# OrientationBoard_LIS303_LIS2DM_L3GD20.net
KiCad netlist of a schematic drawn in Altium Designer
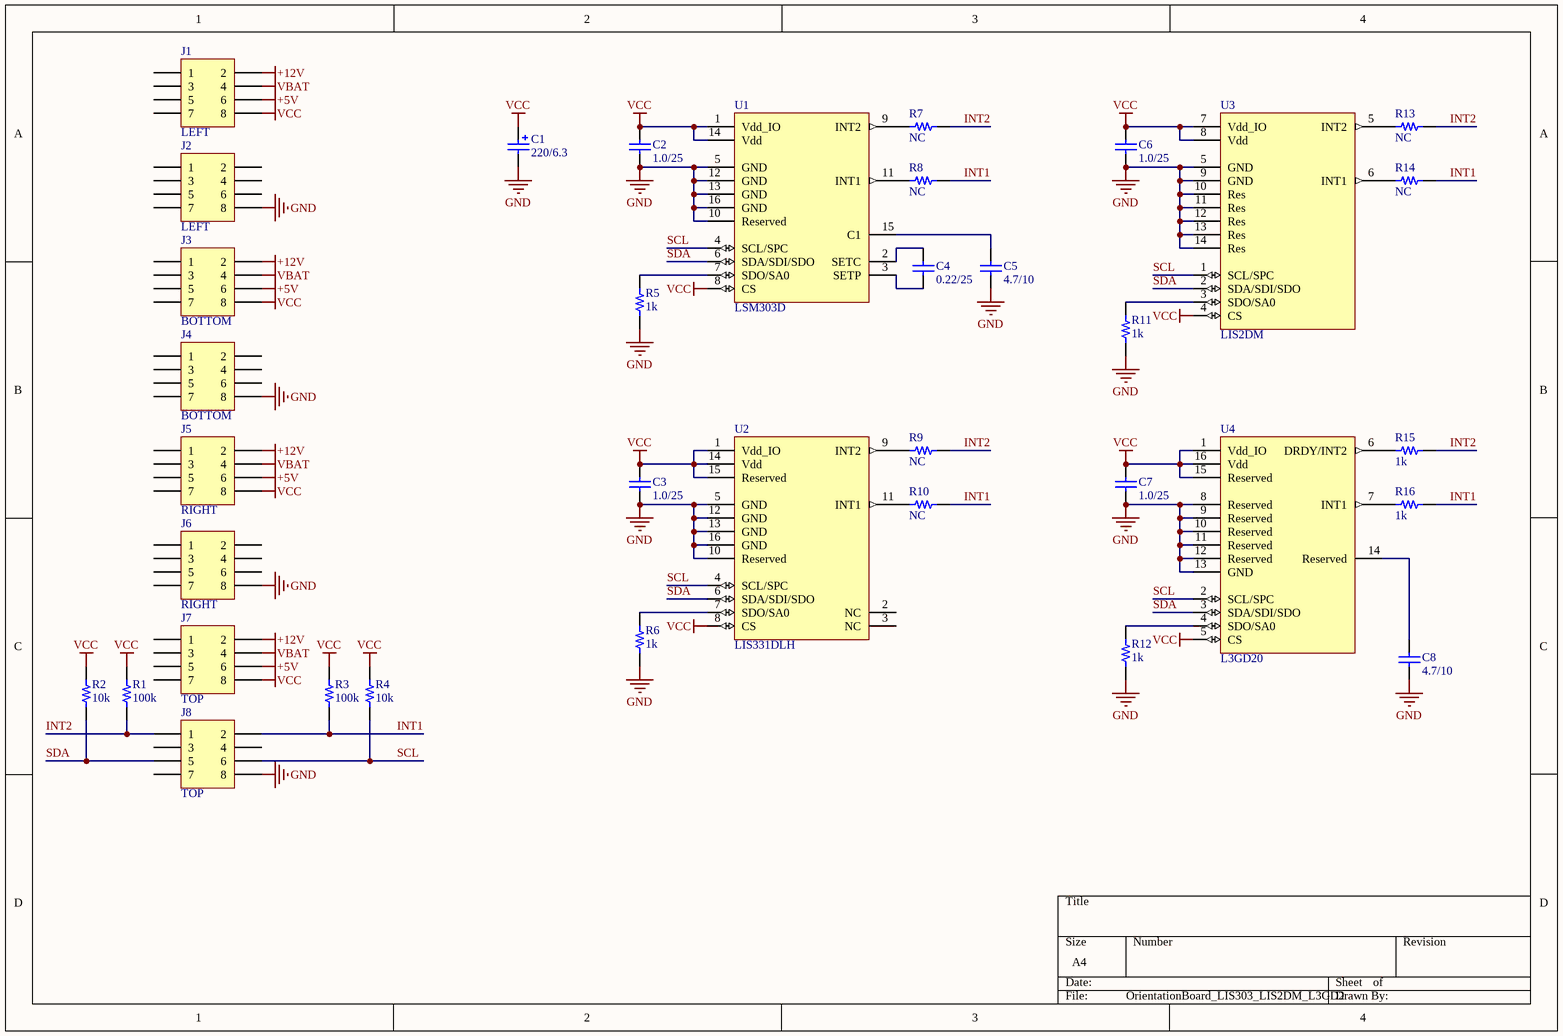
[diagram p0: OrientationBoard_LIS303_LIS2DM_L3GD20.SchDoc]

(export (version "E")
  (design (tool "Eeschema 10.0.6"))
  (components
    (comp (ref "C1")
      (value "220/6.3")
      (footprint "SMC")
      (description "Standard tantalum SMT capacitor, size C")
      (fields
        (field (name "PARTNUMBER") "TAJC")
        (field (name "VOLTAGE") "6.3")
        (field (name "AUTHOR") "oiezhov")
      )
      (libsource (lib "Library") (part "Polar capacitor"))
    )
    (comp (ref "C2")
      (value "1.0/25")
      (footprint "CAP0402")
      (description "Ceramic chip capacitor 0402")
      (fields
        (field (name "PARTNUMBER") "CAP0402")
        (field (name "VOLTAGE") "25")
        (field (name "AUTHOR") "oiezhov")
      )
      (libsource (lib "Library") (part "Capacitor"))
    )
    (comp (ref "C3")
      (value "1.0/25")
      (footprint "CAP0402")
      (description "Ceramic chip capacitor 0402")
      (fields
        (field (name "PARTNUMBER") "CAP0402")
        (field (name "VOLTAGE") "25")
        (field (name "AUTHOR") "oiezhov")
      )
      (libsource (lib "Library") (part "Capacitor"))
    )
    (comp (ref "C4")
      (value "0.22/25")
      (footprint "CAP0402")
      (description "Ceramic chip capacitor 0402")
      (fields
        (field (name "PARTNUMBER") "CAP0402")
        (field (name "VOLTAGE") "25")
        (field (name "AUTHOR") "oiezhov")
      )
      (libsource (lib "Library") (part "Capacitor"))
    )
    (comp (ref "C5")
      (value "4.7/10")
      (footprint "CAP0603")
      (description "Ceramic chip capacitor 0603")
      (fields
        (field (name "PARTNUMBER") "CAP0603")
        (field (name "VOLTAGE") "10")
        (field (name "AUTHOR") "oiezhov")
      )
      (libsource (lib "Library") (part "Capacitor"))
    )
    (comp (ref "C6")
      (value "1.0/25")
      (footprint "CAP0402")
      (description "Ceramic chip capacitor 0402")
      (fields
        (field (name "PARTNUMBER") "CAP0402")
        (field (name "VOLTAGE") "25")
        (field (name "AUTHOR") "oiezhov")
      )
      (libsource (lib "Library") (part "Capacitor"))
    )
    (comp (ref "C7")
      (value "1.0/25")
      (footprint "CAP0402")
      (description "Ceramic chip capacitor 0402")
      (fields
        (field (name "PARTNUMBER") "CAP0402")
        (field (name "VOLTAGE") "25")
        (field (name "AUTHOR") "oiezhov")
      )
      (libsource (lib "Library") (part "Capacitor"))
    )
    (comp (ref "C8")
      (value "4.7/10")
      (footprint "CAP0603")
      (description "Ceramic chip capacitor 0603")
      (fields
        (field (name "PARTNUMBER") "CAP0603")
        (field (name "VOLTAGE") "10")
        (field (name "AUTHOR") "oiezhov")
      )
      (libsource (lib "Library") (part "Capacitor"))
    )
    (comp (ref "J1")
      (value "LEFT")
      (footprint "PBDM-8")
      (description "2x4-pin header, pitch 2.54 mm")
      (fields (field (name "PARTNUMBER") "PBDM-8") (field (name "AUTHOR") "oiezhov"))
      (libsource (lib "Library") (part "8-pin dual row connector"))
    )
    (comp (ref "J2")
      (value "LEFT")
      (footprint "PBDM-8")
      (description "2x4-pin header, pitch 2.54 mm")
      (fields (field (name "PARTNUMBER") "PBDM-8") (field (name "AUTHOR") "oiezhov"))
      (libsource (lib "Library") (part "8-pin dual row connector"))
    )
    (comp (ref "J3")
      (value "BOTTOM")
      (footprint "PBDM-8")
      (description "2x4-pin header, pitch 2.54 mm")
      (fields (field (name "PARTNUMBER") "PBDM-8") (field (name "AUTHOR") "oiezhov"))
      (libsource (lib "Library") (part "8-pin dual row connector"))
    )
    (comp (ref "J4")
      (value "BOTTOM")
      (footprint "PBDM-8")
      (description "2x4-pin header, pitch 2.54 mm")
      (fields (field (name "PARTNUMBER") "PBDM-8") (field (name "AUTHOR") "oiezhov"))
      (libsource (lib "Library") (part "8-pin dual row connector"))
    )
    (comp (ref "J5")
      (value "RIGHT")
      (footprint "PBDM-8")
      (description "2x4-pin header, pitch 2.54 mm")
      (fields (field (name "PARTNUMBER") "PBDM-8") (field (name "AUTHOR") "oiezhov"))
      (libsource (lib "Library") (part "8-pin dual row connector"))
    )
    (comp (ref "J6")
      (value "RIGHT")
      (footprint "PBDM-8")
      (description "2x4-pin header, pitch 2.54 mm")
      (fields (field (name "PARTNUMBER") "PBDM-8") (field (name "AUTHOR") "oiezhov"))
      (libsource (lib "Library") (part "8-pin dual row connector"))
    )
    (comp (ref "J7")
      (value "TOP")
      (footprint "PBDM-8")
      (description "2x4-pin header, pitch 2.54 mm")
      (fields (field (name "PARTNUMBER") "PBDM-8") (field (name "AUTHOR") "oiezhov"))
      (libsource (lib "Library") (part "8-pin dual row connector"))
    )
    (comp (ref "J8")
      (value "TOP")
      (footprint "PBDM-8")
      (description "2x4-pin header, pitch 2.54 mm")
      (fields (field (name "PARTNUMBER") "PBDM-8") (field (name "AUTHOR") "oiezhov"))
      (libsource (lib "Library") (part "8-pin dual row connector"))
    )
    (comp (ref "R1")
      (value "100k")
      (footprint "RES0402")
      (description "Ceramic chip resistor")
      (fields (field (name "PARTNUMBER") "RES0402") (field (name "AUTHOR") "oiezhov"))
      (libsource (lib "Library") (part "Resistor"))
    )
    (comp (ref "R2")
      (value "10k")
      (footprint "RES0402")
      (description "Ceramic chip resistor")
      (fields (field (name "PARTNUMBER") "RES0402") (field (name "AUTHOR") "oiezhov"))
      (libsource (lib "Library") (part "Resistor"))
    )
    (comp (ref "R3")
      (value "100k")
      (footprint "RES0402")
      (description "Ceramic chip resistor")
      (fields (field (name "PARTNUMBER") "RES0402") (field (name "AUTHOR") "oiezhov"))
      (libsource (lib "Library") (part "Resistor"))
    )
    (comp (ref "R4")
      (value "10k")
      (footprint "RES0402")
      (description "Ceramic chip resistor")
      (fields (field (name "PARTNUMBER") "RES0402") (field (name "AUTHOR") "oiezhov"))
      (libsource (lib "Library") (part "Resistor"))
    )
    (comp (ref "R5")
      (value "1k")
      (footprint "RES0402")
      (description "Ceramic chip resistor")
      (fields (field (name "PARTNUMBER") "RES0402") (field (name "AUTHOR") "oiezhov"))
      (libsource (lib "Library") (part "Resistor"))
    )
    (comp (ref "R6")
      (value "1k")
      (footprint "RES0402")
      (description "Ceramic chip resistor")
      (fields (field (name "PARTNUMBER") "RES0402") (field (name "AUTHOR") "oiezhov"))
      (libsource (lib "Library") (part "Resistor"))
    )
    (comp (ref "R7")
      (value "NC")
      (footprint "RES0402")
      (description "Ceramic chip resistor")
      (fields (field (name "PARTNUMBER") "RES0402") (field (name "AUTHOR") "oiezhov"))
      (libsource (lib "Library") (part "Resistor"))
    )
    (comp (ref "R8")
      (value "NC")
      (footprint "RES0402")
      (description "Ceramic chip resistor")
      (fields (field (name "PARTNUMBER") "RES0402") (field (name "AUTHOR") "oiezhov"))
      (libsource (lib "Library") (part "Resistor"))
    )
    (comp (ref "R9")
      (value "NC")
      (footprint "RES0402")
      (description "Ceramic chip resistor")
      (fields (field (name "PARTNUMBER") "RES0402") (field (name "AUTHOR") "oiezhov"))
      (libsource (lib "Library") (part "Resistor"))
    )
    (comp (ref "R10")
      (value "NC")
      (footprint "RES0402")
      (description "Ceramic chip resistor")
      (fields (field (name "PARTNUMBER") "RES0402") (field (name "AUTHOR") "oiezhov"))
      (libsource (lib "Library") (part "Resistor"))
    )
    (comp (ref "R11")
      (value "1k")
      (footprint "RES0402")
      (description "Ceramic chip resistor")
      (fields (field (name "PARTNUMBER") "RES0402") (field (name "AUTHOR") "oiezhov"))
      (libsource (lib "Library") (part "Resistor"))
    )
    (comp (ref "R12")
      (value "1k")
      (footprint "RES0402")
      (description "Ceramic chip resistor")
      (fields (field (name "PARTNUMBER") "RES0402") (field (name "AUTHOR") "oiezhov"))
      (libsource (lib "Library") (part "Resistor"))
    )
    (comp (ref "R13")
      (value "NC")
      (footprint "RES0402")
      (description "Ceramic chip resistor")
      (fields (field (name "PARTNUMBER") "RES0402") (field (name "AUTHOR") "oiezhov"))
      (libsource (lib "Library") (part "Resistor"))
    )
    (comp (ref "R14")
      (value "NC")
      (footprint "RES0402")
      (description "Ceramic chip resistor")
      (fields (field (name "PARTNUMBER") "RES0402") (field (name "AUTHOR") "oiezhov"))
      (libsource (lib "Library") (part "Resistor"))
    )
    (comp (ref "R15")
      (value "1k")
      (footprint "RES0402")
      (description "Ceramic chip resistor")
      (fields (field (name "PARTNUMBER") "RES0402") (field (name "AUTHOR") "oiezhov"))
      (libsource (lib "Library") (part "Resistor"))
    )
    (comp (ref "R16")
      (value "1k")
      (footprint "RES0402")
      (description "Ceramic chip resistor")
      (fields (field (name "PARTNUMBER") "RES0402") (field (name "AUTHOR") "oiezhov"))
      (libsource (lib "Library") (part "Resistor"))
    )
    (comp (ref "U1")
      (value "LSM303D")
      (footprint "LGA16(3x3x1)")
      (description "Ultra-compact high-performance eCompass module: 3D accelerometer and 3D magnetometer")
      (fields (field (name "AUTHOR") "oiezhov"))
      (libsource (lib "Library") (part "LSM303D"))
    )
    (comp (ref "U2")
      (value "LIS331DLH")
      (footprint "LGA16(3x3x1)")
      (description "MEMS digital output motion sensor ultra low-power high performance 3-axes “nano” accelerometer")
      (fields (field (name "AUTHOR") "oiezhov"))
      (libsource (lib "Library") (part "LIS331"))
    )
    (comp (ref "U3")
      (value "LIS2DM")
      (footprint "LGA14(2x2x1)")
      (description "MEMS digital output motion sensor: ultra low-power high performance 3-axis “femto” accelerometer")
      (fields (field (name "AUTHOR") "oiezhov"))
      (libsource (lib "Library") (part "LIS2D"))
    )
    (comp (ref "U4")
      (value "L3GD20")
      (footprint "LGA16(4x4x1)")
      (description "MEMS motion sensor: three-axis digital output gyroscope")
      (fields (field (name "AUTHOR") "oiezhov"))
      (libsource (lib "Library") (part "L3GD20"))
    )
  )
  (nets
    (net (code "1") (name "+5V") (class "Default")
      (node (ref "J1") (pin "6") (pinfunction "6_6") (pintype "passive"))
      (node (ref "J3") (pin "6") (pinfunction "6_6") (pintype "passive"))
      (node (ref "J5") (pin "6") (pinfunction "6_6") (pintype "passive"))
      (node (ref "J7") (pin "6") (pinfunction "6_6") (pintype "passive"))
    )
    (net (code "2") (name "+12V") (class "Default")
      (node (ref "J1") (pin "2") (pinfunction "2_2") (pintype "passive"))
      (node (ref "J3") (pin "2") (pinfunction "2_2") (pintype "passive"))
      (node (ref "J5") (pin "2") (pinfunction "2_2") (pintype "passive"))
      (node (ref "J7") (pin "2") (pinfunction "2_2") (pintype "passive"))
    )
    (net (code "3") (name "/INT1") (class "Default")
      (node (ref "J8") (pin "2") (pinfunction "2_2") (pintype "passive"))
      (node (ref "R10") (pin "1") (pinfunction "1_1") (pintype "passive"))
      (node (ref "R14") (pin "1") (pinfunction "1_1") (pintype "passive"))
      (node (ref "R16") (pin "1") (pinfunction "1_1") (pintype "passive"))
      (node (ref "R3") (pin "1") (pinfunction "1_1") (pintype "passive"))
      (node (ref "R8") (pin "1") (pinfunction "1_1") (pintype "passive"))
    )
    (net (code "4") (name "/INT2") (class "Default")
      (node (ref "J8") (pin "1") (pinfunction "1_1") (pintype "passive"))
      (node (ref "R1") (pin "1") (pinfunction "1_1") (pintype "passive"))
      (node (ref "R13") (pin "1") (pinfunction "1_1") (pintype "passive"))
      (node (ref "R15") (pin "1") (pinfunction "1_1") (pintype "passive"))
      (node (ref "R7") (pin "1") (pinfunction "1_1") (pintype "passive"))
      (node (ref "R9") (pin "1") (pinfunction "1_1") (pintype "passive"))
    )
    (net (code "5") (name "/SCL") (class "Default")
      (node (ref "J8") (pin "6") (pinfunction "6_6") (pintype "passive"))
      (node (ref "R4") (pin "1") (pinfunction "1_1") (pintype "passive"))
      (node (ref "U1") (pin "4") (pinfunction "SCL/SPC_4") (pintype "bidirectional"))
      (node (ref "U2") (pin "4") (pinfunction "SCL/SPC_4") (pintype "bidirectional"))
      (node (ref "U3") (pin "1") (pinfunction "SCL/SPC_1") (pintype "bidirectional"))
      (node (ref "U4") (pin "2") (pinfunction "SCL/SPC_2") (pintype "bidirectional"))
    )
    (net (code "6") (name "/SDA") (class "Default")
      (node (ref "J8") (pin "5") (pinfunction "5_5") (pintype "passive"))
      (node (ref "R2") (pin "1") (pinfunction "1_1") (pintype "passive"))
      (node (ref "U1") (pin "6") (pinfunction "SDA/SDI/SDO_6") (pintype "bidirectional"))
      (node (ref "U2") (pin "6") (pinfunction "SDA/SDI/SDO_6") (pintype "bidirectional"))
      (node (ref "U3") (pin "2") (pinfunction "SDA/SDI/SDO_2") (pintype "bidirectional"))
      (node (ref "U4") (pin "3") (pinfunction "SDA/SDI/SDO_3") (pintype "bidirectional"))
    )
    (net (code "7") (name "GND") (class "Default")
      (node (ref "C1") (pin "1") (pinfunction "1_1") (pintype "passive"))
      (node (ref "C2") (pin "1") (pinfunction "1_1") (pintype "passive"))
      (node (ref "C3") (pin "1") (pinfunction "1_1") (pintype "passive"))
      (node (ref "C5") (pin "1") (pinfunction "1_1") (pintype "passive"))
      (node (ref "C6") (pin "1") (pinfunction "1_1") (pintype "passive"))
      (node (ref "C7") (pin "1") (pinfunction "1_1") (pintype "passive"))
      (node (ref "C8") (pin "1") (pinfunction "1_1") (pintype "passive"))
      (node (ref "J2") (pin "8") (pinfunction "8_8") (pintype "passive"))
      (node (ref "J4") (pin "8") (pinfunction "8_8") (pintype "passive"))
      (node (ref "J6") (pin "8") (pinfunction "8_8") (pintype "passive"))
      (node (ref "J8") (pin "8") (pinfunction "8_8") (pintype "passive"))
      (node (ref "R11") (pin "1") (pinfunction "1_1") (pintype "passive"))
      (node (ref "R12") (pin "1") (pinfunction "1_1") (pintype "passive"))
      (node (ref "R5") (pin "1") (pinfunction "1_1") (pintype "passive"))
      (node (ref "R6") (pin "1") (pinfunction "1_1") (pintype "passive"))
      (node (ref "U1") (pin "10") (pinfunction "Reserved_10") (pintype "passive"))
      (node (ref "U1") (pin "12") (pinfunction "GND_12") (pintype "power_in"))
      (node (ref "U1") (pin "13") (pinfunction "GND_13") (pintype "power_in"))
      (node (ref "U1") (pin "16") (pinfunction "GND_16") (pintype "power_in"))
      (node (ref "U1") (pin "5") (pinfunction "GND_5") (pintype "power_in"))
      (node (ref "U2") (pin "10") (pinfunction "Reserved_10") (pintype "passive"))
      (node (ref "U2") (pin "12") (pinfunction "GND_12") (pintype "power_in"))
      (node (ref "U2") (pin "13") (pinfunction "GND_13") (pintype "power_in"))
      (node (ref "U2") (pin "16") (pinfunction "GND_16") (pintype "power_in"))
      (node (ref "U2") (pin "5") (pinfunction "GND_5") (pintype "power_in"))
      (node (ref "U3") (pin "10") (pinfunction "Res_10") (pintype "passive"))
      (node (ref "U3") (pin "11") (pinfunction "Res_11") (pintype "passive"))
      (node (ref "U3") (pin "12") (pinfunction "Res_12") (pintype "passive"))
      (node (ref "U3") (pin "13") (pinfunction "Res_13") (pintype "passive"))
      (node (ref "U3") (pin "14") (pinfunction "Res_14") (pintype "passive"))
      (node (ref "U3") (pin "5") (pinfunction "GND_5") (pintype "power_in"))
      (node (ref "U3") (pin "9") (pinfunction "GND_9") (pintype "power_in"))
      (node (ref "U4") (pin "10") (pinfunction "Reserved_10") (pintype "passive"))
      (node (ref "U4") (pin "11") (pinfunction "Reserved_11") (pintype "passive"))
      (node (ref "U4") (pin "12") (pinfunction "Reserved_12") (pintype "passive"))
      (node (ref "U4") (pin "13") (pinfunction "GND_13") (pintype "power_in"))
      (node (ref "U4") (pin "8") (pinfunction "Reserved_8") (pintype "passive"))
      (node (ref "U4") (pin "9") (pinfunction "Reserved_9") (pintype "passive"))
    )
    (net (code "8") (name "Net-(C8-Pad2)") (class "Default")
      (node (ref "C8") (pin "2") (pinfunction "2_2") (pintype "passive"))
      (node (ref "U4") (pin "14") (pinfunction "Reserved_14") (pintype "passive"))
    )
    (net (code "9") (name "Net-(U1-C1)") (class "Default")
      (node (ref "C5") (pin "2") (pinfunction "2_2") (pintype "passive"))
      (node (ref "U1") (pin "15") (pinfunction "C1_15") (pintype "passive"))
    )
    (net (code "10") (name "Net-(U1-INT1)") (class "Default")
      (node (ref "R8") (pin "2") (pinfunction "2_2") (pintype "passive"))
      (node (ref "U1") (pin "11") (pinfunction "INT1_11") (pintype "output"))
    )
    (net (code "11") (name "Net-(U1-INT2)") (class "Default")
      (node (ref "R7") (pin "2") (pinfunction "2_2") (pintype "passive"))
      (node (ref "U1") (pin "9") (pinfunction "INT2_9") (pintype "output"))
    )
    (net (code "12") (name "Net-(U1-SDO{slash}SA0)") (class "Default")
      (node (ref "R5") (pin "2") (pinfunction "2_2") (pintype "passive"))
      (node (ref "U1") (pin "7") (pinfunction "SDO/SA0_7") (pintype "bidirectional"))
    )
    (net (code "13") (name "Net-(U1-SETC)") (class "Default")
      (node (ref "C4") (pin "2") (pinfunction "2_2") (pintype "passive"))
      (node (ref "U1") (pin "2") (pinfunction "SETC_2") (pintype "passive"))
    )
    (net (code "14") (name "Net-(U1-SETP)") (class "Default")
      (node (ref "C4") (pin "1") (pinfunction "1_1") (pintype "passive"))
      (node (ref "U1") (pin "3") (pinfunction "SETP_3") (pintype "passive"))
    )
    (net (code "15") (name "Net-(U2-INT1)") (class "Default")
      (node (ref "R10") (pin "2") (pinfunction "2_2") (pintype "passive"))
      (node (ref "U2") (pin "11") (pinfunction "INT1_11") (pintype "output"))
    )
    (net (code "16") (name "Net-(U2-INT2)") (class "Default")
      (node (ref "R9") (pin "2") (pinfunction "2_2") (pintype "passive"))
      (node (ref "U2") (pin "9") (pinfunction "INT2_9") (pintype "output"))
    )
    (net (code "17") (name "Net-(U2-SDO{slash}SA0)") (class "Default")
      (node (ref "R6") (pin "2") (pinfunction "2_2") (pintype "passive"))
      (node (ref "U2") (pin "7") (pinfunction "SDO/SA0_7") (pintype "bidirectional"))
    )
    (net (code "18") (name "Net-(U3-INT1)") (class "Default")
      (node (ref "R14") (pin "2") (pinfunction "2_2") (pintype "passive"))
      (node (ref "U3") (pin "6") (pinfunction "INT1_6") (pintype "output"))
    )
    (net (code "19") (name "Net-(U3-INT2)") (class "Default")
      (node (ref "R13") (pin "2") (pinfunction "2_2") (pintype "passive"))
      (node (ref "U3") (pin "5") (pinfunction "INT2_5") (pintype "output"))
    )
    (net (code "20") (name "Net-(U3-SDO{slash}SA0)") (class "Default")
      (node (ref "R11") (pin "2") (pinfunction "2_2") (pintype "passive"))
      (node (ref "U3") (pin "3") (pinfunction "SDO/SA0_3") (pintype "bidirectional"))
    )
    (net (code "21") (name "Net-(U4-DRDY{slash}INT2)") (class "Default")
      (node (ref "R15") (pin "2") (pinfunction "2_2") (pintype "passive"))
      (node (ref "U4") (pin "6") (pinfunction "DRDY/INT2_6") (pintype "output"))
    )
    (net (code "22") (name "Net-(U4-INT1)") (class "Default")
      (node (ref "R16") (pin "2") (pinfunction "2_2") (pintype "passive"))
      (node (ref "U4") (pin "7") (pinfunction "INT1_7") (pintype "output"))
    )
    (net (code "23") (name "Net-(U4-SDO{slash}SA0)") (class "Default")
      (node (ref "R12") (pin "2") (pinfunction "2_2") (pintype "passive"))
      (node (ref "U4") (pin "4") (pinfunction "SDO/SA0_4") (pintype "bidirectional"))
    )
    (net (code "24") (name "VBAT") (class "Default")
      (node (ref "J1") (pin "4") (pinfunction "4_4") (pintype "passive"))
      (node (ref "J3") (pin "4") (pinfunction "4_4") (pintype "passive"))
      (node (ref "J5") (pin "4") (pinfunction "4_4") (pintype "passive"))
      (node (ref "J7") (pin "4") (pinfunction "4_4") (pintype "passive"))
    )
    (net (code "25") (name "VCC") (class "Default")
      (node (ref "C1") (pin "2") (pinfunction "2_2") (pintype "passive"))
      (node (ref "C2") (pin "2") (pinfunction "2_2") (pintype "passive"))
      (node (ref "C3") (pin "2") (pinfunction "2_2") (pintype "passive"))
      (node (ref "C6") (pin "2") (pinfunction "2_2") (pintype "passive"))
      (node (ref "C7") (pin "2") (pinfunction "2_2") (pintype "passive"))
      (node (ref "J1") (pin "8") (pinfunction "8_8") (pintype "passive"))
      (node (ref "J3") (pin "8") (pinfunction "8_8") (pintype "passive"))
      (node (ref "J5") (pin "8") (pinfunction "8_8") (pintype "passive"))
      (node (ref "J7") (pin "8") (pinfunction "8_8") (pintype "passive"))
      (node (ref "R1") (pin "2") (pinfunction "2_2") (pintype "passive"))
      (node (ref "R2") (pin "2") (pinfunction "2_2") (pintype "passive"))
      (node (ref "R3") (pin "2") (pinfunction "2_2") (pintype "passive"))
      (node (ref "R4") (pin "2") (pinfunction "2_2") (pintype "passive"))
      (node (ref "U1") (pin "1") (pinfunction "Vdd_IO_1") (pintype "power_in"))
      (node (ref "U1") (pin "14") (pinfunction "Vdd_14") (pintype "power_in"))
      (node (ref "U1") (pin "8") (pinfunction "CS_8") (pintype "bidirectional"))
      (node (ref "U2") (pin "1") (pinfunction "Vdd_IO_1") (pintype "power_in"))
      (node (ref "U2") (pin "14") (pinfunction "Vdd_14") (pintype "power_in"))
      (node (ref "U2") (pin "15") (pinfunction "Reserved_15") (pintype "passive"))
      (node (ref "U2") (pin "8") (pinfunction "CS_8") (pintype "bidirectional"))
      (node (ref "U3") (pin "4") (pinfunction "CS_4") (pintype "bidirectional"))
      (node (ref "U3") (pin "7") (pinfunction "Vdd_IO_7") (pintype "power_in"))
      (node (ref "U3") (pin "8") (pinfunction "Vdd_8") (pintype "power_in"))
      (node (ref "U4") (pin "1") (pinfunction "Vdd_IO_1") (pintype "power_in"))
      (node (ref "U4") (pin "15") (pinfunction "Reserved_15") (pintype "passive"))
      (node (ref "U4") (pin "16") (pinfunction "Vdd_16") (pintype "power_in"))
      (node (ref "U4") (pin "5") (pinfunction "CS_5") (pintype "bidirectional"))
    )
    (net (code "26") (name "unconnected-(J1-Pad1)") (class "Default")
      (node (ref "J1") (pin "1") (pinfunction "1_1") (pintype "passive"))
    )
    (net (code "27") (name "unconnected-(J1-Pad3)") (class "Default")
      (node (ref "J1") (pin "3") (pinfunction "3_3") (pintype "passive"))
    )
    (net (code "28") (name "unconnected-(J1-Pad5)") (class "Default")
      (node (ref "J1") (pin "5") (pinfunction "5_5") (pintype "passive"))
    )
    (net (code "29") (name "unconnected-(J1-Pad7)") (class "Default")
      (node (ref "J1") (pin "7") (pinfunction "7_7") (pintype "passive"))
    )
    (net (code "30") (name "unconnected-(J2-Pad1)") (class "Default")
      (node (ref "J2") (pin "1") (pinfunction "1_1") (pintype "passive"))
    )
    (net (code "31") (name "unconnected-(J2-Pad2)") (class "Default")
      (node (ref "J2") (pin "2") (pinfunction "2_2") (pintype "passive"))
    )
    (net (code "32") (name "unconnected-(J2-Pad3)") (class "Default")
      (node (ref "J2") (pin "3") (pinfunction "3_3") (pintype "passive"))
    )
    (net (code "33") (name "unconnected-(J2-Pad4)") (class "Default")
      (node (ref "J2") (pin "4") (pinfunction "4_4") (pintype "passive"))
    )
    (net (code "34") (name "unconnected-(J2-Pad5)") (class "Default")
      (node (ref "J2") (pin "5") (pinfunction "5_5") (pintype "passive"))
    )
    (net (code "35") (name "unconnected-(J2-Pad6)") (class "Default")
      (node (ref "J2") (pin "6") (pinfunction "6_6") (pintype "passive"))
    )
    (net (code "36") (name "unconnected-(J2-Pad7)") (class "Default")
      (node (ref "J2") (pin "7") (pinfunction "7_7") (pintype "passive"))
    )
    (net (code "37") (name "unconnected-(J3-Pad1)") (class "Default")
      (node (ref "J3") (pin "1") (pinfunction "1_1") (pintype "passive"))
    )
    (net (code "38") (name "unconnected-(J3-Pad3)") (class "Default")
      (node (ref "J3") (pin "3") (pinfunction "3_3") (pintype "passive"))
    )
    (net (code "39") (name "unconnected-(J3-Pad5)") (class "Default")
      (node (ref "J3") (pin "5") (pinfunction "5_5") (pintype "passive"))
    )
    (net (code "40") (name "unconnected-(J3-Pad7)") (class "Default")
      (node (ref "J3") (pin "7") (pinfunction "7_7") (pintype "passive"))
    )
    (net (code "41") (name "unconnected-(J4-Pad1)") (class "Default")
      (node (ref "J4") (pin "1") (pinfunction "1_1") (pintype "passive"))
    )
    (net (code "42") (name "unconnected-(J4-Pad2)") (class "Default")
      (node (ref "J4") (pin "2") (pinfunction "2_2") (pintype "passive"))
    )
    (net (code "43") (name "unconnected-(J4-Pad3)") (class "Default")
      (node (ref "J4") (pin "3") (pinfunction "3_3") (pintype "passive"))
    )
    (net (code "44") (name "unconnected-(J4-Pad4)") (class "Default")
      (node (ref "J4") (pin "4") (pinfunction "4_4") (pintype "passive"))
    )
    (net (code "45") (name "unconnected-(J4-Pad5)") (class "Default")
      (node (ref "J4") (pin "5") (pinfunction "5_5") (pintype "passive"))
    )
    (net (code "46") (name "unconnected-(J4-Pad6)") (class "Default")
      (node (ref "J4") (pin "6") (pinfunction "6_6") (pintype "passive"))
    )
    (net (code "47") (name "unconnected-(J4-Pad7)") (class "Default")
      (node (ref "J4") (pin "7") (pinfunction "7_7") (pintype "passive"))
    )
    (net (code "48") (name "unconnected-(J5-Pad1)") (class "Default")
      (node (ref "J5") (pin "1") (pinfunction "1_1") (pintype "passive"))
    )
    (net (code "49") (name "unconnected-(J5-Pad3)") (class "Default")
      (node (ref "J5") (pin "3") (pinfunction "3_3") (pintype "passive"))
    )
    (net (code "50") (name "unconnected-(J5-Pad5)") (class "Default")
      (node (ref "J5") (pin "5") (pinfunction "5_5") (pintype "passive"))
    )
    (net (code "51") (name "unconnected-(J5-Pad7)") (class "Default")
      (node (ref "J5") (pin "7") (pinfunction "7_7") (pintype "passive"))
    )
    (net (code "52") (name "unconnected-(J6-Pad1)") (class "Default")
      (node (ref "J6") (pin "1") (pinfunction "1_1") (pintype "passive"))
    )
    (net (code "53") (name "unconnected-(J6-Pad2)") (class "Default")
      (node (ref "J6") (pin "2") (pinfunction "2_2") (pintype "passive"))
    )
    (net (code "54") (name "unconnected-(J6-Pad3)") (class "Default")
      (node (ref "J6") (pin "3") (pinfunction "3_3") (pintype "passive"))
    )
    (net (code "55") (name "unconnected-(J6-Pad4)") (class "Default")
      (node (ref "J6") (pin "4") (pinfunction "4_4") (pintype "passive"))
    )
    (net (code "56") (name "unconnected-(J6-Pad5)") (class "Default")
      (node (ref "J6") (pin "5") (pinfunction "5_5") (pintype "passive"))
    )
    (net (code "57") (name "unconnected-(J6-Pad6)") (class "Default")
      (node (ref "J6") (pin "6") (pinfunction "6_6") (pintype "passive"))
    )
    (net (code "58") (name "unconnected-(J6-Pad7)") (class "Default")
      (node (ref "J6") (pin "7") (pinfunction "7_7") (pintype "passive"))
    )
    (net (code "59") (name "unconnected-(J7-Pad1)") (class "Default")
      (node (ref "J7") (pin "1") (pinfunction "1_1") (pintype "passive"))
    )
    (net (code "60") (name "unconnected-(J7-Pad3)") (class "Default")
      (node (ref "J7") (pin "3") (pinfunction "3_3") (pintype "passive"))
    )
    (net (code "61") (name "unconnected-(J7-Pad5)") (class "Default")
      (node (ref "J7") (pin "5") (pinfunction "5_5") (pintype "passive"))
    )
    (net (code "62") (name "unconnected-(J7-Pad7)") (class "Default")
      (node (ref "J7") (pin "7") (pinfunction "7_7") (pintype "passive"))
    )
    (net (code "63") (name "unconnected-(J8-Pad3)") (class "Default")
      (node (ref "J8") (pin "3") (pinfunction "3_3") (pintype "passive"))
    )
    (net (code "64") (name "unconnected-(J8-Pad4)") (class "Default")
      (node (ref "J8") (pin "4") (pinfunction "4_4") (pintype "passive"))
    )
    (net (code "65") (name "unconnected-(J8-Pad7)") (class "Default")
      (node (ref "J8") (pin "7") (pinfunction "7_7") (pintype "passive"))
    )
    (net (code "66") (name "unconnected-(U2-NC-Pad2)") (class "Default")
      (node (ref "U2") (pin "2") (pinfunction "NC_2") (pintype "passive"))
    )
    (net (code "67") (name "unconnected-(U2-NC-Pad3)") (class "Default")
      (node (ref "U2") (pin "3") (pinfunction "NC_3") (pintype "passive"))
    )
  )
)
